# mcu.net
KiCad netlist of a schematic drawn in Altium Designer
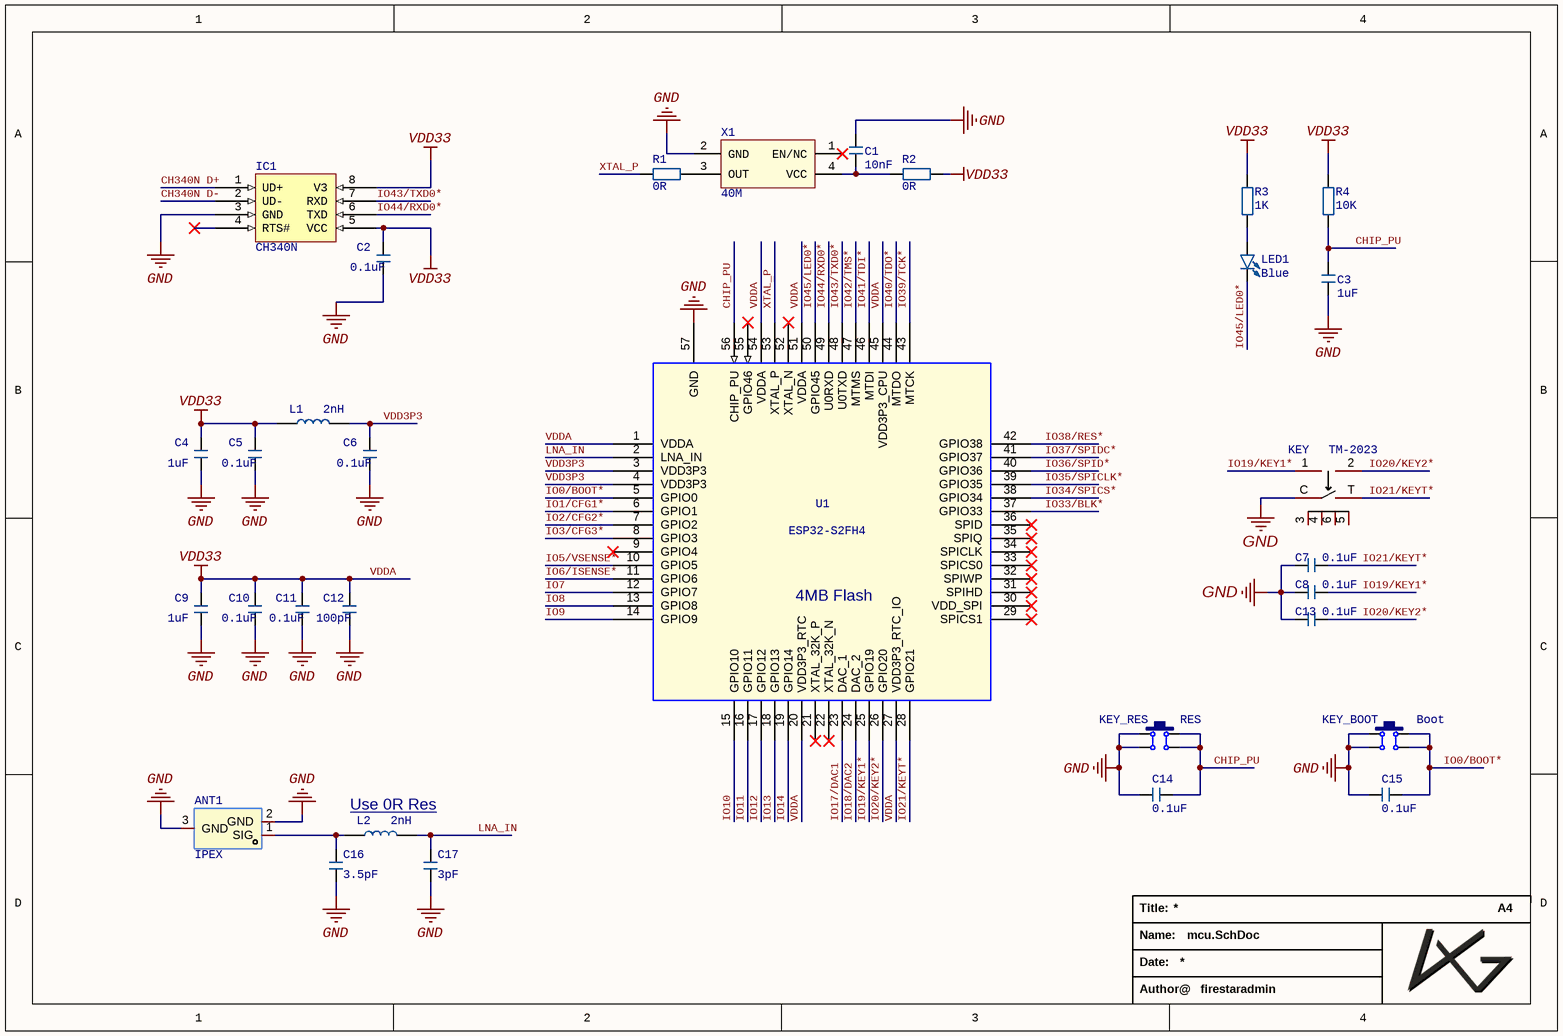
[diagram p0: mcu.SchDoc]

(export (version "E")
  (design (tool "Eeschema 10.0.6"))
  (components
    (comp (ref "ANT1")
      (value "IPEX")
      (footprint "IPEX-3Pin")
      (description "IPEX 天线座子")
      (libsource (lib "SCH-天线") (part "IPEX"))
    )
    (comp (ref "C1")
      (value "10nF")
      (footprint "C 0603_L")
      (description "无极性贴片电容")
      (fields (field (name "版权归属") "源创客"))
      (libsource (lib "SCH-电阻-电容-电感") (part "C"))
    )
    (comp (ref "C2")
      (value "0.1uF")
      (footprint "C 0603_L")
      (description "无极性贴片电容")
      (fields (field (name "版权归属") "源创客"))
      (libsource (lib "SCH-电阻-电容-电感") (part "C"))
    )
    (comp (ref "C3")
      (value "1uF")
      (footprint "C 0603_L")
      (description "无极性贴片电容")
      (fields (field (name "版权归属") "源创客"))
      (libsource (lib "SCH-电阻-电容-电感") (part "C"))
    )
    (comp (ref "C4")
      (value "1uF")
      (footprint "C 0603_L")
      (description "无极性贴片电容")
      (fields (field (name "版权归属") "源创客"))
      (libsource (lib "SCH-电阻-电容-电感") (part "C"))
    )
    (comp (ref "C5")
      (value "0.1uF")
      (footprint "C 0603_L")
      (description "无极性贴片电容")
      (fields (field (name "版权归属") "源创客"))
      (libsource (lib "SCH-电阻-电容-电感") (part "C"))
    )
    (comp (ref "C6")
      (value "0.1uF")
      (footprint "C 0603_L")
      (description "无极性贴片电容")
      (fields (field (name "版权归属") "源创客"))
      (libsource (lib "SCH-电阻-电容-电感") (part "C"))
    )
    (comp (ref "C7")
      (value "0.1uF")
      (footprint "C 0603_L")
      (description "无极性贴片电容")
      (fields (field (name "版权归属") "源创客"))
      (libsource (lib "SCH-电阻-电容-电感") (part "C"))
    )
    (comp (ref "C8")
      (value "0.1uF")
      (footprint "C 0603_L")
      (description "无极性贴片电容")
      (fields (field (name "版权归属") "源创客"))
      (libsource (lib "SCH-电阻-电容-电感") (part "C"))
    )
    (comp (ref "C9")
      (value "1uF")
      (footprint "C 0603_L")
      (description "无极性贴片电容")
      (fields (field (name "版权归属") "源创客"))
      (libsource (lib "SCH-电阻-电容-电感") (part "C"))
    )
    (comp (ref "C10")
      (value "0.1uF")
      (footprint "C 0603_L")
      (description "无极性贴片电容")
      (fields (field (name "版权归属") "源创客"))
      (libsource (lib "SCH-电阻-电容-电感") (part "C"))
    )
    (comp (ref "C11")
      (value "0.1uF")
      (footprint "C 0603_L")
      (description "无极性贴片电容")
      (fields (field (name "版权归属") "源创客"))
      (libsource (lib "SCH-电阻-电容-电感") (part "C"))
    )
    (comp (ref "C12")
      (value "100pF")
      (footprint "C 0603_L")
      (description "无极性贴片电容")
      (fields (field (name "版权归属") "源创客"))
      (libsource (lib "SCH-电阻-电容-电感") (part "C"))
    )
    (comp (ref "C13")
      (value "0.1uF")
      (footprint "C 0603_L")
      (description "无极性贴片电容")
      (fields (field (name "版权归属") "源创客"))
      (libsource (lib "SCH-电阻-电容-电感") (part "C"))
    )
    (comp (ref "C14")
      (value "0.1uF")
      (footprint "C 0603_L")
      (description "无极性贴片电容")
      (fields (field (name "版权归属") "源创客"))
      (libsource (lib "SCH-电阻-电容-电感") (part "C"))
    )
    (comp (ref "C15")
      (value "0.1uF")
      (footprint "C 0603_L")
      (description "无极性贴片电容")
      (fields (field (name "版权归属") "源创客"))
      (libsource (lib "SCH-电阻-电容-电感") (part "C"))
    )
    (comp (ref "C16")
      (value "3.5pF")
      (footprint "C 0603_L")
      (description "无极性贴片电容")
      (fields (field (name "版权归属") "源创客"))
      (libsource (lib "SCH-电阻-电容-电感") (part "C"))
    )
    (comp (ref "C17")
      (value "3pF")
      (footprint "C 0603_L")
      (description "无极性贴片电容")
      (fields (field (name "版权归属") "源创客"))
      (libsource (lib "SCH-电阻-电容-电感") (part "C"))
    )
    (comp (ref "IC1")
      (value "CH340N")
      (footprint "SOP8_N")
      (description "USB 转串口芯片 CH330/CH340N")
      (libsource (lib "SCH-IC芯片") (part "CH340N"))
    )
    (comp (ref "KEY")
      (value "TM-2023")
      (footprint "TM-2023")
      (description "三角拨轮开关")
      (libsource (lib "SCH-按键-开关") (part "TM-2023"))
    )
    (comp (ref "KEY_BOOT")
      (value "Boot")
      (footprint "TSMD-3*4*2.5")
      (description "TS-3x4x2.5mm-4pin 轻触按键")
      (libsource (lib "SCH-按键-开关") (part "TS-3x4x2.5mm-4pin"))
    )
    (comp (ref "KEY_RES")
      (value "RES")
      (footprint "TSMD-3*4*2.5")
      (description "TS-3x4x2.5mm-4pin 轻触按键")
      (libsource (lib "SCH-按键-开关") (part "TS-3x4x2.5mm-4pin"))
    )
    (comp (ref "L1")
      (value "2nH")
      (footprint "L 0603-L")
      (description "小功率贴片电感")
      (fields (field (name "版权归属") "源创客"))
      (libsource (lib "SCH-电阻-电容-电感") (part "L"))
    )
    (comp (ref "L2")
      (value "2nH")
      (footprint "L 0603-L")
      (description "小功率贴片电感")
      (fields (field (name "版权归属") "源创客"))
      (libsource (lib "SCH-电阻-电容-电感") (part "L"))
    )
    (comp (ref "LED1")
      (value "Blue")
      (footprint "LED 0603B")
      (description "贴片LED")
      (fields (field (name "版权归属") "源创客"))
      (libsource (lib "SCH-LED") (part "LED-SMD"))
    )
    (comp (ref "R1")
      (value "0R")
      (footprint "R 0603_L")
      (description "贴片电阻")
      (fields (field (name "版权归属") "源创客"))
      (libsource (lib "SCH-电阻-电容-电感") (part "R"))
    )
    (comp (ref "R2")
      (value "0R")
      (footprint "R 0603_L")
      (description "贴片电阻")
      (fields (field (name "版权归属") "源创客"))
      (libsource (lib "SCH-电阻-电容-电感") (part "R"))
    )
    (comp (ref "R3")
      (value "1K")
      (footprint "R 0603_L")
      (description "贴片电阻")
      (fields (field (name "版权归属") "源创客"))
      (libsource (lib "SCH-电阻-电容-电感") (part "R"))
    )
    (comp (ref "R4")
      (value "10K")
      (footprint "R 0603_L")
      (description "贴片电阻")
      (fields (field (name "版权归属") "源创客"))
      (libsource (lib "SCH-电阻-电容-电感") (part "R"))
    )
    (comp (ref "U1")
      (value "ESP32-S2FH4")
      (footprint "QFN-56_L7.0-W7.0-P0.40-TL-EP4.0")
      (description "单核 32 位 LX7 微处理器的 SoC, 240Mhz , 4MB Flash")
      (libsource (lib "SCH-ESP系列") (part "ESP32-S2FH4"))
    )
    (comp (ref "X1")
      (value "40M")
      (footprint "OSC 3225-4P")
      (description "4脚有源晶振")
      (fields (field (name "版权归属") "源创客"))
      (libsource (lib "SCH- 保险丝-晶振") (part "XTAL-ACT-4P"))
    )
  )
  (nets
    (net (code "1") (name "/CH340N D+") (class "Default")
      (node (ref "IC1") (pin "1") (pinfunction "UD+_1") (pintype "input"))
    )
    (net (code "2") (name "/CH340N D-") (class "Default")
      (node (ref "IC1") (pin "2") (pinfunction "UD-_2") (pintype "input"))
    )
    (net (code "3") (name "/CHIP_PU") (class "Default")
      (node (ref "C14") (pin "2") (pinfunction "2_2") (pintype "passive"))
      (node (ref "C3") (pin "1") (pinfunction "1_1") (pintype "passive"))
      (node (ref "KEY_RES") (pin "3") (pinfunction "3_3") (pintype "passive"))
      (node (ref "KEY_RES") (pin "4") (pinfunction "4_4") (pintype "passive"))
      (node (ref "R4") (pin "1") (pinfunction "1_1") (pintype "passive"))
      (node (ref "U1") (pin "56") (pinfunction "CHIP_PU_56") (pintype "input"))
    )
    (net (code "4") (name "/IO0{slash}BOOT*") (class "Default")
      (node (ref "C15") (pin "2") (pinfunction "2_2") (pintype "passive"))
      (node (ref "KEY_BOOT") (pin "3") (pinfunction "3_3") (pintype "passive"))
      (node (ref "KEY_BOOT") (pin "4") (pinfunction "4_4") (pintype "passive"))
      (node (ref "U1") (pin "5") (pinfunction "GPIO0_5") (pintype "passive"))
    )
    (net (code "5") (name "/IO1{slash}CFG1*") (class "Default")
      (node (ref "U1") (pin "6") (pinfunction "GPIO1_6") (pintype "passive"))
    )
    (net (code "6") (name "/IO2{slash}CFG2*") (class "Default")
      (node (ref "U1") (pin "7") (pinfunction "GPIO2_7") (pintype "passive"))
    )
    (net (code "7") (name "/IO3{slash}CFG3*") (class "Default")
      (node (ref "U1") (pin "8") (pinfunction "GPIO3_8") (pintype "passive"))
    )
    (net (code "8") (name "/IO5{slash}VSENSE*") (class "Default")
      (node (ref "U1") (pin "10") (pinfunction "GPIO5_10") (pintype "passive"))
    )
    (net (code "9") (name "/IO6{slash}ISENSE*") (class "Default")
      (node (ref "U1") (pin "11") (pinfunction "GPIO6_11") (pintype "passive"))
    )
    (net (code "10") (name "/IO7") (class "Default")
      (node (ref "U1") (pin "12") (pinfunction "GPIO7_12") (pintype "passive"))
    )
    (net (code "11") (name "/IO8") (class "Default")
      (node (ref "U1") (pin "13") (pinfunction "GPIO8_13") (pintype "passive"))
    )
    (net (code "12") (name "/IO9") (class "Default")
      (node (ref "U1") (pin "14") (pinfunction "GPIO9_14") (pintype "passive"))
    )
    (net (code "13") (name "/IO10") (class "Default")
      (node (ref "U1") (pin "15") (pinfunction "GPIO10_15") (pintype "passive"))
    )
    (net (code "14") (name "/IO11") (class "Default")
      (node (ref "U1") (pin "16") (pinfunction "GPIO11_16") (pintype "passive"))
    )
    (net (code "15") (name "/IO12") (class "Default")
      (node (ref "U1") (pin "17") (pinfunction "GPIO12_17") (pintype "passive"))
    )
    (net (code "16") (name "/IO13") (class "Default")
      (node (ref "U1") (pin "18") (pinfunction "GPIO13_18") (pintype "passive"))
    )
    (net (code "17") (name "/IO14") (class "Default")
      (node (ref "U1") (pin "19") (pinfunction "GPIO14_19") (pintype "passive"))
    )
    (net (code "18") (name "/IO17{slash}DAC1") (class "Default")
      (node (ref "U1") (pin "23") (pinfunction "DAC_1_23") (pintype "passive"))
    )
    (net (code "19") (name "/IO18{slash}DAC2") (class "Default")
      (node (ref "U1") (pin "24") (pinfunction "DAC_2_24") (pintype "passive"))
    )
    (net (code "20") (name "/IO19{slash}KEY1*") (class "Default")
      (node (ref "C8") (pin "2") (pinfunction "2_2") (pintype "passive"))
      (node (ref "KEY") (pin "1") (pinfunction "1_1") (pintype "passive"))
      (node (ref "U1") (pin "25") (pinfunction "GPIO19_25") (pintype "passive"))
    )
    (net (code "21") (name "/IO20{slash}KEY2*") (class "Default")
      (node (ref "C13") (pin "2") (pinfunction "2_2") (pintype "passive"))
      (node (ref "KEY") (pin "2") (pinfunction "2_2") (pintype "passive"))
      (node (ref "U1") (pin "26") (pinfunction "GPIO20_26") (pintype "passive"))
    )
    (net (code "22") (name "/IO21{slash}KEYT*") (class "Default")
      (node (ref "C7") (pin "2") (pinfunction "2_2") (pintype "passive"))
      (node (ref "KEY") (pin "T") (pinfunction "T_T") (pintype "passive"))
      (node (ref "U1") (pin "28") (pinfunction "GPIO21_28") (pintype "passive"))
    )
    (net (code "23") (name "/IO33{slash}BLK*") (class "Default")
      (node (ref "U1") (pin "37") (pinfunction "GPIO33_37") (pintype "passive"))
    )
    (net (code "24") (name "/IO34{slash}SPICS*") (class "Default")
      (node (ref "U1") (pin "38") (pinfunction "GPIO34_38") (pintype "passive"))
    )
    (net (code "25") (name "/IO35{slash}SPICLK*") (class "Default")
      (node (ref "U1") (pin "39") (pinfunction "GPIO35_39") (pintype "passive"))
    )
    (net (code "26") (name "/IO36{slash}SPID*") (class "Default")
      (node (ref "U1") (pin "40") (pinfunction "GPIO36_40") (pintype "passive"))
    )
    (net (code "27") (name "/IO37{slash}SPIDC*") (class "Default")
      (node (ref "U1") (pin "41") (pinfunction "GPIO37_41") (pintype "passive"))
    )
    (net (code "28") (name "/IO38{slash}RES*") (class "Default")
      (node (ref "U1") (pin "42") (pinfunction "GPIO38_42") (pintype "passive"))
    )
    (net (code "29") (name "/IO39{slash}TCK*") (class "Default")
      (node (ref "U1") (pin "43") (pinfunction "MTCK_43") (pintype "passive"))
    )
    (net (code "30") (name "/IO40{slash}TDO*") (class "Default")
      (node (ref "U1") (pin "44") (pinfunction "MTDO_44") (pintype "passive"))
    )
    (net (code "31") (name "/IO41{slash}TDI*") (class "Default")
      (node (ref "U1") (pin "46") (pinfunction "MTDI_46") (pintype "passive"))
    )
    (net (code "32") (name "/IO42{slash}TMS*") (class "Default")
      (node (ref "U1") (pin "47") (pinfunction "MTMS_47") (pintype "passive"))
    )
    (net (code "33") (name "/IO43{slash}TXD0*") (class "Default")
      (node (ref "IC1") (pin "7") (pinfunction "RXD_7") (pintype "input"))
      (node (ref "U1") (pin "48") (pinfunction "U0TXD_48") (pintype "passive"))
    )
    (net (code "34") (name "/IO44{slash}RXD0*") (class "Default")
      (node (ref "IC1") (pin "6") (pinfunction "TXD_6") (pintype "input"))
      (node (ref "U1") (pin "49") (pinfunction "U0RXD_49") (pintype "passive"))
    )
    (net (code "35") (name "/IO45{slash}LED0*") (class "Default")
      (node (ref "LED1") (pin "2") (pinfunction "K_2") (pintype "passive"))
      (node (ref "U1") (pin "50") (pinfunction "GPIO45_50") (pintype "passive"))
    )
    (net (code "36") (name "/LNA_IN") (class "Default")
      (node (ref "C17") (pin "2") (pinfunction "2_2") (pintype "passive"))
      (node (ref "L2") (pin "2") (pinfunction "2_2") (pintype "passive"))
      (node (ref "U1") (pin "2") (pinfunction "LNA_IN_2") (pintype "passive"))
    )
    (net (code "37") (name "/VDD3P3") (class "Default")
      (node (ref "C6") (pin "2") (pinfunction "2_2") (pintype "passive"))
      (node (ref "L1") (pin "2") (pinfunction "2_2") (pintype "passive"))
      (node (ref "U1") (pin "3") (pinfunction "VDD3P3_3") (pintype "power_in"))
      (node (ref "U1") (pin "4") (pinfunction "VDD3P3_4") (pintype "power_in"))
    )
    (net (code "38") (name "/XTAL_P") (class "Default")
      (node (ref "R1") (pin "1") (pinfunction "1_1") (pintype "passive"))
      (node (ref "U1") (pin "53") (pinfunction "XTAL_P_53") (pintype "passive"))
    )
    (net (code "39") (name "GND") (class "Default")
      (node (ref "ANT1") (pin "2") (pinfunction "GND_2") (pintype "passive"))
      (node (ref "ANT1") (pin "3") (pinfunction "GND_3") (pintype "passive"))
      (node (ref "C1") (pin "2") (pinfunction "2_2") (pintype "passive"))
      (node (ref "C10") (pin "1") (pinfunction "1_1") (pintype "passive"))
      (node (ref "C11") (pin "1") (pinfunction "1_1") (pintype "passive"))
      (node (ref "C12") (pin "1") (pinfunction "1_1") (pintype "passive"))
      (node (ref "C13") (pin "1") (pinfunction "1_1") (pintype "passive"))
      (node (ref "C14") (pin "1") (pinfunction "1_1") (pintype "passive"))
      (node (ref "C15") (pin "1") (pinfunction "1_1") (pintype "passive"))
      (node (ref "C16") (pin "1") (pinfunction "1_1") (pintype "passive"))
      (node (ref "C17") (pin "1") (pinfunction "1_1") (pintype "passive"))
      (node (ref "C2") (pin "1") (pinfunction "1_1") (pintype "passive"))
      (node (ref "C3") (pin "2") (pinfunction "2_2") (pintype "passive"))
      (node (ref "C4") (pin "1") (pinfunction "1_1") (pintype "passive"))
      (node (ref "C5") (pin "1") (pinfunction "1_1") (pintype "passive"))
      (node (ref "C6") (pin "1") (pinfunction "1_1") (pintype "passive"))
      (node (ref "C7") (pin "1") (pinfunction "1_1") (pintype "passive"))
      (node (ref "C8") (pin "1") (pinfunction "1_1") (pintype "passive"))
      (node (ref "C9") (pin "1") (pinfunction "1_1") (pintype "passive"))
      (node (ref "IC1") (pin "3") (pinfunction "GND_3") (pintype "input"))
      (node (ref "KEY") (pin "C") (pinfunction "C_C") (pintype "passive"))
      (node (ref "KEY_BOOT") (pin "1") (pinfunction "1_1") (pintype "passive"))
      (node (ref "KEY_BOOT") (pin "2") (pinfunction "2_2") (pintype "passive"))
      (node (ref "KEY_RES") (pin "1") (pinfunction "1_1") (pintype "passive"))
      (node (ref "KEY_RES") (pin "2") (pinfunction "2_2") (pintype "passive"))
      (node (ref "U1") (pin "57") (pinfunction "GND_57") (pintype "power_in"))
      (node (ref "X1") (pin "2") (pinfunction "GND_2") (pintype "passive"))
    )
    (net (code "40") (name "Net-(ANT1-SIG)") (class "Default")
      (node (ref "ANT1") (pin "1") (pinfunction "SIG_1") (pintype "passive"))
      (node (ref "C16") (pin "2") (pinfunction "2_2") (pintype "passive"))
      (node (ref "L2") (pin "1") (pinfunction "1_1") (pintype "passive"))
    )
    (net (code "41") (name "Net-(LED1-A)") (class "Default")
      (node (ref "LED1") (pin "1") (pinfunction "A_1") (pintype "passive"))
      (node (ref "R3") (pin "1") (pinfunction "1_1") (pintype "passive"))
    )
    (net (code "42") (name "Net-(X1-OUT)") (class "Default")
      (node (ref "R1") (pin "2") (pinfunction "2_2") (pintype "passive"))
      (node (ref "X1") (pin "3") (pinfunction "OUT_3") (pintype "passive"))
    )
    (net (code "43") (name "Net-(X1-VCC)") (class "Default")
      (node (ref "C1") (pin "1") (pinfunction "1_1") (pintype "passive"))
      (node (ref "R2") (pin "1") (pinfunction "1_1") (pintype "passive"))
      (node (ref "X1") (pin "4") (pinfunction "VCC_4") (pintype "passive"))
    )
    (net (code "44") (name "VDD33") (class "Default")
      (node (ref "C10") (pin "2") (pinfunction "2_2") (pintype "passive"))
      (node (ref "C11") (pin "2") (pinfunction "2_2") (pintype "passive"))
      (node (ref "C12") (pin "2") (pinfunction "2_2") (pintype "passive"))
      (node (ref "C2") (pin "2") (pinfunction "2_2") (pintype "passive"))
      (node (ref "C4") (pin "2") (pinfunction "2_2") (pintype "passive"))
      (node (ref "C5") (pin "2") (pinfunction "2_2") (pintype "passive"))
      (node (ref "C9") (pin "2") (pinfunction "2_2") (pintype "passive"))
      (node (ref "IC1") (pin "5") (pinfunction "VCC_5") (pintype "input"))
      (node (ref "IC1") (pin "8") (pinfunction "V3_8") (pintype "input"))
      (node (ref "L1") (pin "1") (pinfunction "1_1") (pintype "passive"))
      (node (ref "R2") (pin "2") (pinfunction "2_2") (pintype "passive"))
      (node (ref "R3") (pin "2") (pinfunction "2_2") (pintype "passive"))
      (node (ref "R4") (pin "2") (pinfunction "2_2") (pintype "passive"))
      (node (ref "U1") (pin "1") (pinfunction "VDDA_1") (pintype "power_in"))
      (node (ref "U1") (pin "20") (pinfunction "VDD3P3_RTC_20") (pintype "power_in"))
      (node (ref "U1") (pin "27") (pinfunction "VDD3P3_RTC_IO_27") (pintype "power_in"))
      (node (ref "U1") (pin "45") (pinfunction "VDD3P3_CPU_45") (pintype "power_in"))
      (node (ref "U1") (pin "51") (pinfunction "VDDA_51") (pintype "power_in"))
      (node (ref "U1") (pin "54") (pinfunction "VDDA_54") (pintype "power_in"))
    )
    (net (code "45") (name "unconnected-(IC1-RTS#-Pad4)") (class "Default")
      (node (ref "IC1") (pin "4") (pinfunction "RTS#_4") (pintype "input+no_connect"))
    )
    (net (code "46") (name "unconnected-(KEY-Pad3)") (class "Default")
      (node (ref "KEY") (pin "3") (pinfunction "3_3") (pintype "passive"))
    )
    (net (code "47") (name "unconnected-(KEY-Pad4)") (class "Default")
      (node (ref "KEY") (pin "4") (pinfunction "4_4") (pintype "passive"))
    )
    (net (code "48") (name "unconnected-(KEY-Pad5)") (class "Default")
      (node (ref "KEY") (pin "5") (pinfunction "5_5") (pintype "passive"))
    )
    (net (code "49") (name "unconnected-(KEY-Pad6)") (class "Default")
      (node (ref "KEY") (pin "6") (pinfunction "6_6") (pintype "passive"))
    )
    (net (code "50") (name "unconnected-(U1-GPIO4-Pad9)") (class "Default")
      (node (ref "U1") (pin "9") (pinfunction "GPIO4_9") (pintype "passive+no_connect"))
    )
    (net (code "51") (name "unconnected-(U1-GPIO46-Pad55)") (class "Default")
      (node (ref "U1") (pin "55") (pinfunction "GPIO46_55") (pintype "input+no_connect"))
    )
    (net (code "52") (name "unconnected-(U1-SPICLK-Pad34)") (class "Default")
      (node (ref "U1") (pin "34") (pinfunction "SPICLK_34") (pintype "passive+no_connect"))
    )
    (net (code "53") (name "unconnected-(U1-SPICS0-Pad33)") (class "Default")
      (node (ref "U1") (pin "33") (pinfunction "SPICS0_33") (pintype "passive+no_connect"))
    )
    (net (code "54") (name "unconnected-(U1-SPICS1-Pad29)") (class "Default")
      (node (ref "U1") (pin "29") (pinfunction "SPICS1_29") (pintype "passive+no_connect"))
    )
    (net (code "55") (name "unconnected-(U1-SPID-Pad36)") (class "Default")
      (node (ref "U1") (pin "36") (pinfunction "SPID_36") (pintype "passive+no_connect"))
    )
    (net (code "56") (name "unconnected-(U1-SPIHD-Pad31)") (class "Default")
      (node (ref "U1") (pin "31") (pinfunction "SPIHD_31") (pintype "passive+no_connect"))
    )
    (net (code "57") (name "unconnected-(U1-SPIQ-Pad35)") (class "Default")
      (node (ref "U1") (pin "35") (pinfunction "SPIQ_35") (pintype "passive+no_connect"))
    )
    (net (code "58") (name "unconnected-(U1-SPIWP-Pad32)") (class "Default")
      (node (ref "U1") (pin "32") (pinfunction "SPIWP_32") (pintype "passive+no_connect"))
    )
    (net (code "59") (name "unconnected-(U1-VDD_SPI-Pad30)") (class "Default")
      (node (ref "U1") (pin "30") (pinfunction "VDD_SPI_30") (pintype "power_in+no_connect"))
    )
    (net (code "60") (name "unconnected-(U1-XTAL_32K_N-Pad22)") (class "Default")
      (node (ref "U1") (pin "22") (pinfunction "XTAL_32K_N_22") (pintype "passive+no_connect"))
    )
    (net (code "61") (name "unconnected-(U1-XTAL_32K_P-Pad21)") (class "Default")
      (node (ref "U1") (pin "21") (pinfunction "XTAL_32K_P_21") (pintype "passive+no_connect"))
    )
    (net (code "62") (name "unconnected-(U1-XTAL_N-Pad52)") (class "Default")
      (node (ref "U1") (pin "52") (pinfunction "XTAL_N_52") (pintype "passive+no_connect"))
    )
    (net (code "63") (name "unconnected-(X1-EN{slash}NC-Pad1)") (class "Default")
      (node (ref "X1") (pin "1") (pinfunction "EN/NC_1") (pintype "passive+no_connect"))
    )
  )
)
